# OMODRI_Support.net
KiCad netlist of a schematic drawn in Altium Designer
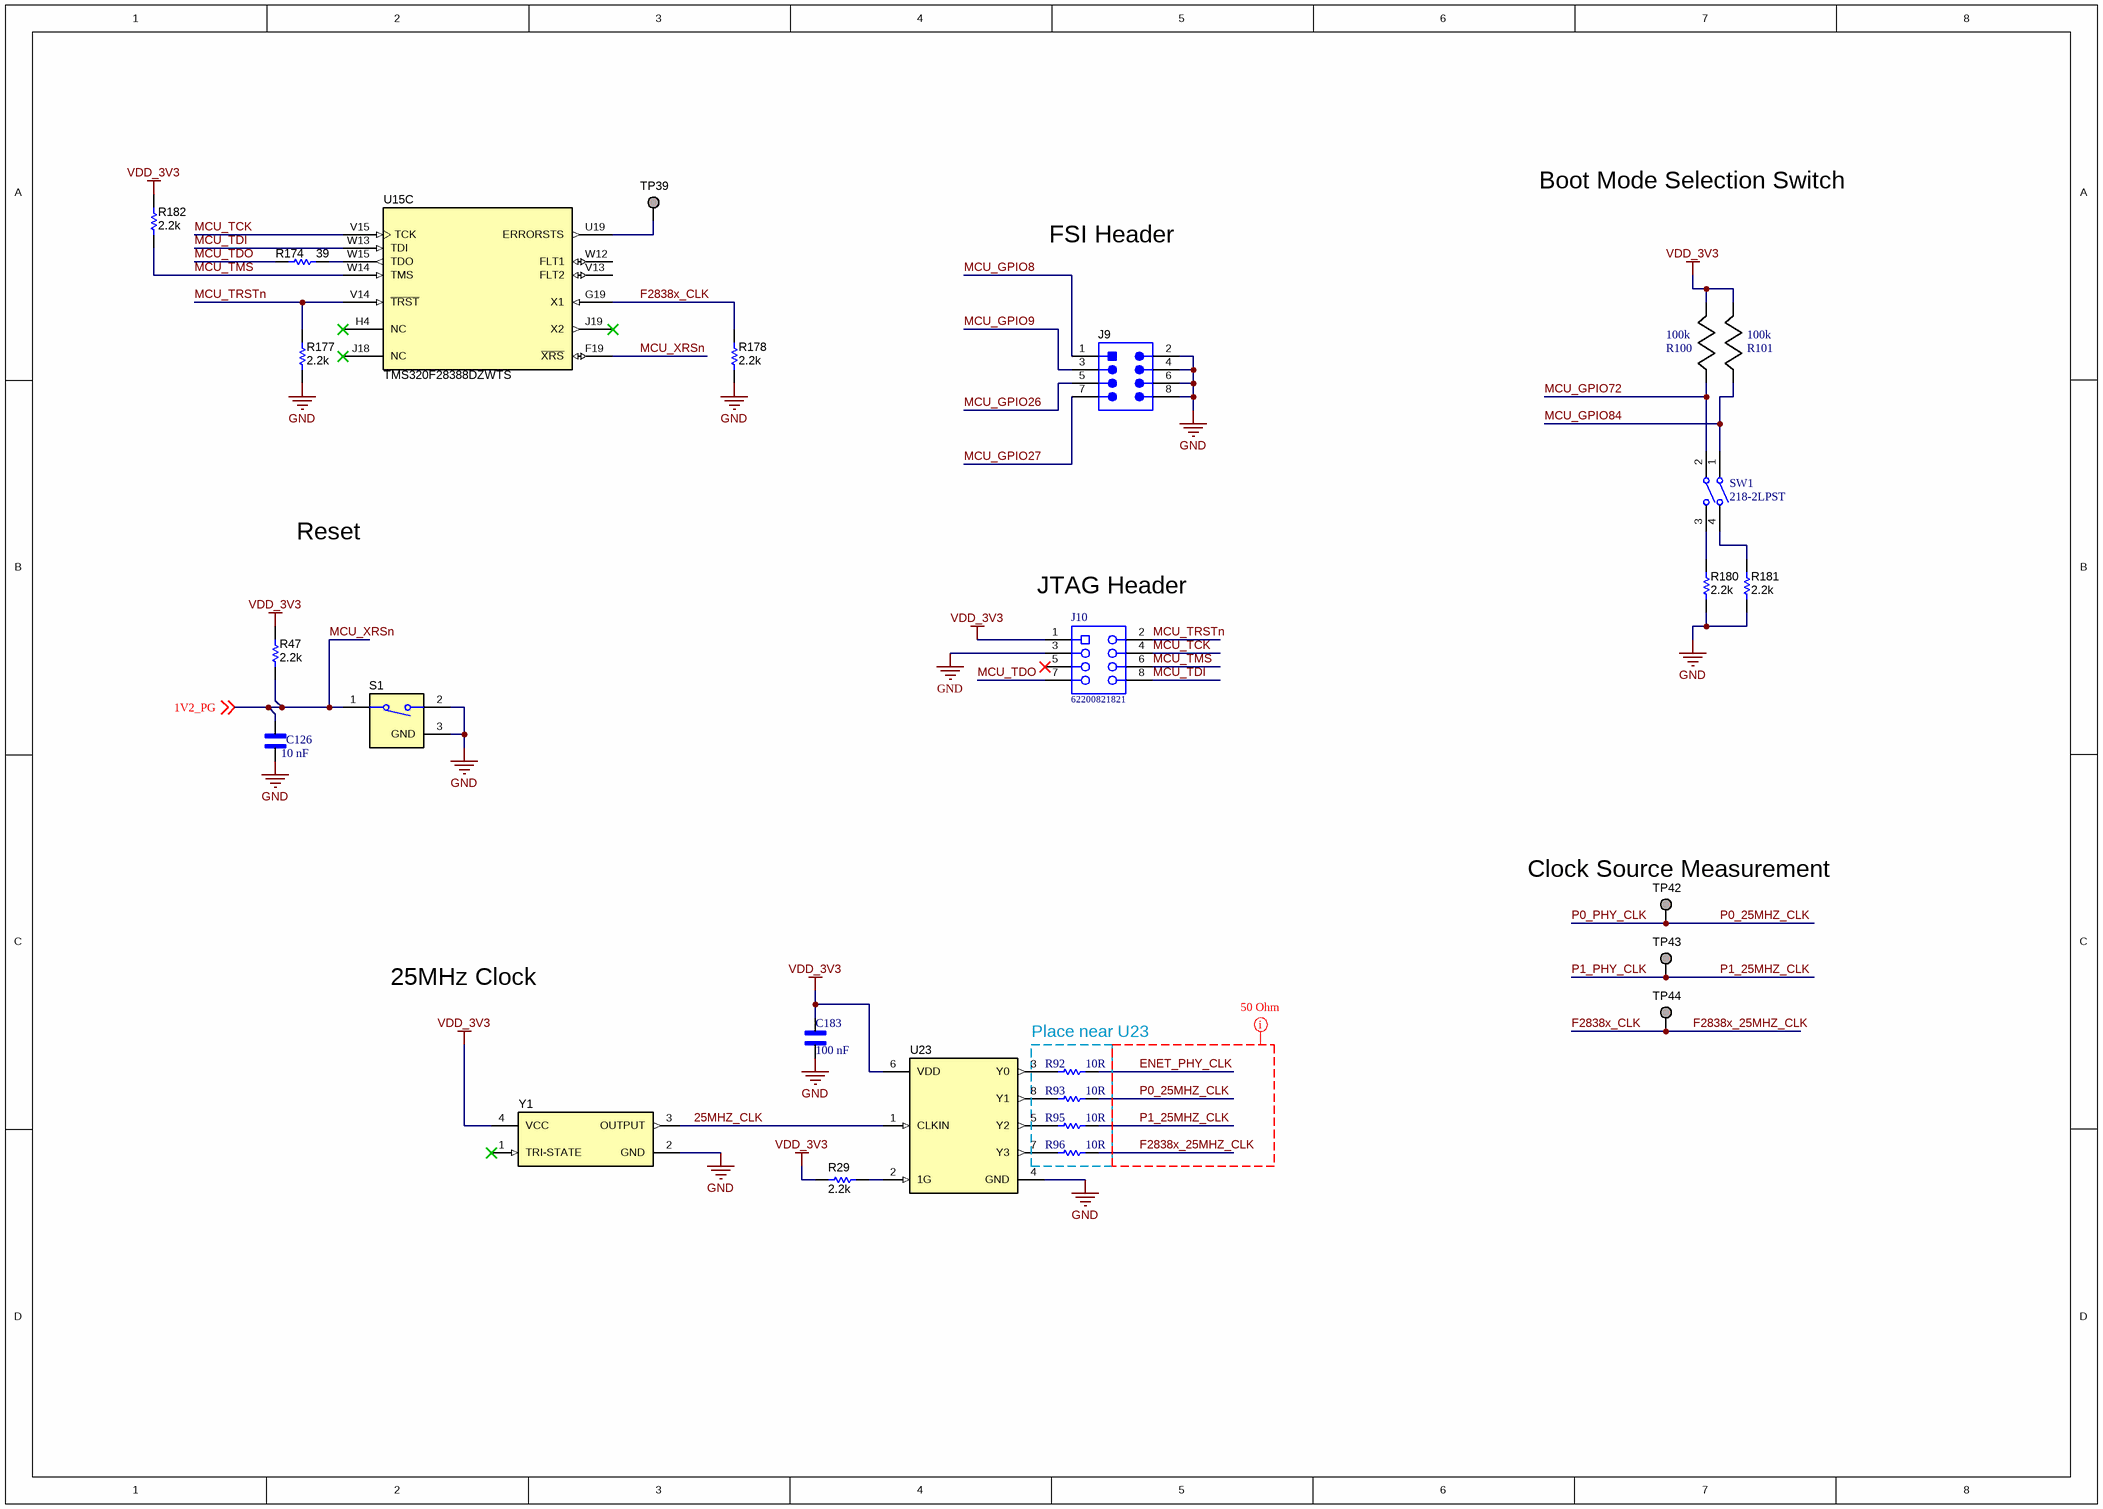
[diagram p0: OMODRI_Support.SchDoc]

(export (version "E")
  (design (tool "Eeschema 10.0.6"))
  (components
    (comp (ref "C126")
      (value "10 nF")
      (footprint "CAPC0603X33N")
      (description "SMD Capacitor X7R_EIA_ with Capacitance: 10000pF Tol. 10%. Rated Voltage: 25Vdc")
      (fields (field (name "MP") "GRM033R71E103KE14D") (field (name "MF") "Murata"))
      (libsource (lib "GRM033R71E103KE14D") (part "GRM033R71E103KE14D"))
    )
    (comp (ref "C183")
      (value "100 nF")
      (footprint "CAPC0603X33N")
      (description "SMD Capacitor X5R_EIA_ with Capacitance: 0.10uF Tol. 10%. Rated Voltage: 25Vdc")
      (fields (field (name "MF") "Murata") (field (name "MP") "GRM033R61E104KE14D"))
      (libsource (lib "GRM033R61E104KE14D") (part "GRM033R61E104KE14D"))
    )
    (comp (ref "J9")
      (value "TMM-104-01-T-D")
      (footprint "Samtec_TMM-104-01-x-D")
      (description "Header, 2mm, 4x2, Tin, TH")
      (fields (field (name "MANUFACTURER") "Samtec"))
      (libsource (lib "Altium Vault - TI") (part "Header_4x2"))
    )
    (comp (ref "J10")
      (value "62200821821")
      (footprint "62200821821")
      (description "THT Vertical Socket Header WR-PHD, Pitch 1.27 mm, Dual Row, 8 pins")
      (fields (field (name "MANUFACTURER") "Wurth Elektronik") (field (name "PUBLISHER") "WurthElektronik"))
      (libsource (lib "Altium Content Vault") (part "WE-CN-2P-F-R8"))
    )
    (comp (ref "R29")
      (value "CRCW04022K20JNED")
      (footprint "0402")
      (description "RES, 2.2 k, 5%, 0.063 W, AEC-Q200 Grade 0, 0402")
      (fields (field (name "MANUFACTURER") "Vishay-Dale") (field (name "VALUEDISPLAYED") "2.2k"))
      (libsource (lib "Altium Vault - TI") (part "Resistor"))
    )
    (comp (ref "R47")
      (value "CRCW04022K20JNED")
      (footprint "0402")
      (description "RES, 2.2 k, 5%, 0.063 W, AEC-Q200 Grade 0, 0402")
      (fields (field (name "MANUFACTURER") "Vishay-Dale") (field (name "VALUEDISPLAYED") "2.2k"))
      (libsource (lib "Altium Vault - TI") (part "Resistor"))
    )
    (comp (ref "R92")
      (value "CRCW040210R0FKEDHP")
      (footprint "RESC1005X40X25ML05T10")
      (description "SMD Chip Resistor, 0402 [1005 Metric], 10 ohm, CRCW-HP e3 Series, 50 V, Thick Film, 200 mW")
      (fields
        (field (name "MANUFACTURER") "Vishay Dale")
        (field (name "TOLERANCE") "1%")
        (field (name "RESISTANCE") "10R")
      )
      (libsource (lib "Vishay-Resistor") (part "CRCW040210R0FKEDHP"))
    )
    (comp (ref "R93")
      (value "CRCW040210R0FKEDHP")
      (footprint "RESC1005X40X25ML05T10")
      (description "SMD Chip Resistor, 0402 [1005 Metric], 10 ohm, CRCW-HP e3 Series, 50 V, Thick Film, 200 mW")
      (fields
        (field (name "MANUFACTURER") "Vishay Dale")
        (field (name "TOLERANCE") "1%")
        (field (name "RESISTANCE") "10R")
      )
      (libsource (lib "Vishay-Resistor") (part "CRCW040210R0FKEDHP"))
    )
    (comp (ref "R95")
      (value "CRCW040210R0FKEDHP")
      (footprint "RESC1005X40X25ML05T10")
      (description "SMD Chip Resistor, 0402 [1005 Metric], 10 ohm, CRCW-HP e3 Series, 50 V, Thick Film, 200 mW")
      (fields
        (field (name "MANUFACTURER") "Vishay Dale")
        (field (name "TOLERANCE") "1%")
        (field (name "RESISTANCE") "10R")
      )
      (libsource (lib "Vishay-Resistor") (part "CRCW040210R0FKEDHP"))
    )
    (comp (ref "R96")
      (value "CRCW040210R0FKEDHP")
      (footprint "RESC1005X40X25ML05T10")
      (description "SMD Chip Resistor, 0402 [1005 Metric], 10 ohm, CRCW-HP e3 Series, 50 V, Thick Film, 200 mW")
      (fields
        (field (name "MANUFACTURER") "Vishay Dale")
        (field (name "TOLERANCE") "1%")
        (field (name "RESISTANCE") "10R")
      )
      (libsource (lib "Vishay-Resistor") (part "CRCW040210R0FKEDHP"))
    )
    (comp (ref "R100")
      (value "CRCW0402100KFKED")
      (footprint "0402")
      (description "Res Thick Film 0402 100K Ohm 1% 1/16W 100ppm/C Molded SMD Paper T/R")
      (fields
        (field (name "MANUFACTURER") "Vishay")
        (field (name "TOLERANCE") "1%")
        (field (name "RESISTANCE") "100k")
      )
      (libsource (lib "TI_TPS_6208833") (part "CRCW0402100KFKED"))
    )
    (comp (ref "R101")
      (value "CRCW0402100KFKED")
      (footprint "0402")
      (description "Res Thick Film 0402 100K Ohm 1% 1/16W 100ppm/C Molded SMD Paper T/R")
      (fields
        (field (name "MANUFACTURER") "Vishay")
        (field (name "TOLERANCE") "1%")
        (field (name "RESISTANCE") "100k")
      )
      (libsource (lib "TI_TPS_6208833") (part "CRCW0402100KFKED"))
    )
    (comp (ref "R174")
      (value "CRCW040239R0JNED")
      (footprint "0402")
      (description "RES, 39, 5%, 0.063 W, AEC-Q200 Grade 0, 0402")
      (fields (field (name "MANUFACTURER") "Vishay-Dale") (field (name "VALUEDISPLAYED") "39"))
      (libsource (lib "Altium Vault - TI") (part "Resistor"))
    )
    (comp (ref "R177")
      (value "CRCW04022K20JNED")
      (footprint "0402")
      (description "RES, 2.2 k, 5%, 0.063 W, AEC-Q200 Grade 0, 0402")
      (fields (field (name "MANUFACTURER") "Vishay-Dale") (field (name "VALUEDISPLAYED") "2.2k"))
      (libsource (lib "Altium Vault - TI") (part "Resistor"))
    )
    (comp (ref "R178")
      (value "CRCW04022K20JNED")
      (footprint "0402")
      (description "RES, 2.2 k, 5%, 0.063 W, AEC-Q200 Grade 0, 0402")
      (fields (field (name "MANUFACTURER") "Vishay-Dale") (field (name "VALUEDISPLAYED") "2.2k"))
      (libsource (lib "Altium Vault - TI") (part "Resistor"))
    )
    (comp (ref "R180")
      (value "CRCW04022K20JNED")
      (footprint "0402")
      (description "RES, 2.2 k, 5%, 0.063 W, AEC-Q200 Grade 0, 0402")
      (fields (field (name "VALUEDISPLAYED") "2.2k") (field (name "MANUFACTURER") "Vishay-Dale"))
      (libsource (lib "Altium Vault - TI") (part "Resistor"))
    )
    (comp (ref "R181")
      (value "CRCW04022K20JNED")
      (footprint "0402")
      (description "RES, 2.2 k, 5%, 0.063 W, AEC-Q200 Grade 0, 0402")
      (fields (field (name "VALUEDISPLAYED") "2.2k") (field (name "MANUFACTURER") "Vishay-Dale"))
      (libsource (lib "Altium Vault - TI") (part "Resistor"))
    )
    (comp (ref "R182")
      (value "CRCW04022K20JNED")
      (footprint "0402")
      (description "RES, 2.2 k, 5%, 0.063 W, AEC-Q200 Grade 0, 0402")
      (fields (field (name "MANUFACTURER") "Vishay-Dale") (field (name "VALUEDISPLAYED") "2.2k"))
      (libsource (lib "Altium Vault - TI") (part "Resistor"))
    )
    (comp (ref "S1")
      (value "B3U-1100P")
      (footprint "SW_B3U-1100P")
      (description "Switch, SPST-NO, Off-Mom, 12 V, SMD")
      (fields
        (field (name "MANUFACTURER") "Omron Electronic Components")
        (field (name "PUBLISHER") "Texas Instruments")
      )
      (libsource (lib "Altium Vault - TI") (part "Switch_PushButton_GND3"))
    )
    (comp (ref "SW1")
      (value "218-2LPST")
      (footprint "CTS-218-2LPST_V")
      (description "Half Pitch DIP Switch Auto Placeable, 25 mA, 24 V, -55 to 85 degC, 4-Pin SMD, RoHS, Tube")
      (fields (field (name "MANUFACTURER") "CTS Corporation"))
      (libsource (lib "Altium Content Vault") (part "SW-SPST-4_C"))
    )
    (comp (ref "TP39")
      (value "TESTPOINT")
      (footprint "TP_50MIL-25MILHOLE")
      (description "TEST POINT.  No entry in BOM.")
      (libsource (lib "Altium Vault - TI") (part "CMP-0078143-2"))
    )
    (comp (ref "TP42")
      (value "TESTPOINT")
      (footprint "TP_50MIL-25MILHOLE")
      (description "TEST POINT.  No entry in BOM.")
      (libsource (lib "Altium Vault - TI") (part "CMP-0078143-2"))
    )
    (comp (ref "TP43")
      (value "TESTPOINT")
      (footprint "TP_50MIL-25MILHOLE")
      (description "TEST POINT.  No entry in BOM.")
      (libsource (lib "Altium Vault - TI") (part "CMP-0078143-2"))
    )
    (comp (ref "TP44")
      (value "TESTPOINT")
      (footprint "TP_50MIL-25MILHOLE")
      (description "TEST POINT.  No entry in BOM.")
      (libsource (lib "Altium Vault - TI") (part "CMP-0078143-2"))
    )
    (comp (ref "U15")
      (value "TMS320F28388DZWTS")
      (footprint "ZWT0337A")
      (description "TMS320F28388DZWTS, ZWT0337A (NFBGA-337)")
      (fields
        (field (name "PARTNUMBER") "TMS320F28388DZWTS")
        (field (name "MANUFACTURER") "Texas Instruments")
      )
      (libsource (lib "Altium Vault - TI") (part "TMS320F28388"))
    )
    (comp (ref "U23")
      (value "CDCLVC1104PW")
      (footprint "PW0008A_N")
      (description "Low Jitter, 1:4 LVCMOS Fan-out Clock Buffer, PW0008A (TSSOP-8)")
      (fields
        (field (name "MANUFACTURER") "Texas Instruments")
        (field (name "PUBLISHER") "Texas Instruments")
      )
      (libsource (lib "Altium Vault - TI") (part "CDCLVC1104"))
    )
    (comp (ref "Y1")
      (value "ECS-2520S33-250-FN-TR")
      (footprint "ECS_ECS-2520S")
      (description "Oscillator, 25 MHz, 15 pF, SMD")
      (fields (field (name "MANUFACTURER") "ECS Inc."))
      (libsource (lib "Altium Vault - TI") (part "OSC_4P_1_TRI-STATE"))
    )
  )
  (nets
    (net (code "1") (name "/25MHZ_CLK") (class "Default")
      (node (ref "U23") (pin "1") (pinfunction "CLKIN_1") (pintype "input"))
      (node (ref "Y1") (pin "3") (pinfunction "OUTPUT_3") (pintype "output"))
    )
    (net (code "2") (name "/ENET_PHY_CLK") (class "Default")
      (node (ref "R92") (pin "2") (pinfunction "2_2") (pintype "passive"))
    )
    (net (code "3") (name "/F2838x_25MHZ_CLK") (class "Default")
      (node (ref "R178") (pin "2") (pinfunction "2_2") (pintype "passive"))
      (node (ref "R96") (pin "2") (pinfunction "2_2") (pintype "passive"))
      (node (ref "TP44") (pin "1") (pintype "passive"))
      (node (ref "U15") (pin "G19") (pinfunction "X1_G19") (pintype "input"))
    )
    (net (code "4") (name "/MCU_GPIO8") (class "Default")
      (node (ref "J9") (pin "1") (pinfunction "1_1") (pintype "passive"))
    )
    (net (code "5") (name "/MCU_GPIO9") (class "Default")
      (node (ref "J9") (pin "3") (pinfunction "3_3") (pintype "passive"))
    )
    (net (code "6") (name "/MCU_GPIO26") (class "Default")
      (node (ref "J9") (pin "5") (pinfunction "5_5") (pintype "passive"))
    )
    (net (code "7") (name "/MCU_GPIO27") (class "Default")
      (node (ref "J9") (pin "7") (pinfunction "7_7") (pintype "passive"))
    )
    (net (code "8") (name "/MCU_GPIO72") (class "Default")
      (node (ref "R100") (pin "2") (pinfunction "2_2") (pintype "passive"))
      (node (ref "SW1") (pin "2") (pinfunction "2_2") (pintype "passive"))
    )
    (net (code "9") (name "/MCU_GPIO84") (class "Default")
      (node (ref "R101") (pin "2") (pinfunction "2_2") (pintype "passive"))
      (node (ref "SW1") (pin "1") (pinfunction "1_1") (pintype "passive"))
    )
    (net (code "10") (name "/MCU_TCK") (class "Default")
      (node (ref "J10") (pin "4") (pinfunction "4_4") (pintype "passive"))
      (node (ref "U15") (pin "V15") (pinfunction "TCK_V15") (pintype "input"))
    )
    (net (code "11") (name "/MCU_TDI") (class "Default")
      (node (ref "J10") (pin "8") (pinfunction "8_8") (pintype "passive"))
      (node (ref "U15") (pin "W13") (pinfunction "TDI_W13") (pintype "input"))
    )
    (net (code "12") (name "/MCU_TDO") (class "Default")
      (node (ref "J10") (pin "7") (pinfunction "7_7") (pintype "passive"))
      (node (ref "R174") (pin "1") (pinfunction "1_1") (pintype "passive"))
    )
    (net (code "13") (name "/MCU_TMS") (class "Default")
      (node (ref "J10") (pin "6") (pinfunction "6_6") (pintype "passive"))
      (node (ref "R182") (pin "1") (pinfunction "1_1") (pintype "passive"))
      (node (ref "U15") (pin "W14") (pinfunction "TMS_W14") (pintype "input"))
    )
    (net (code "14") (name "/MCU_TRSTn") (class "Default")
      (node (ref "J10") (pin "2") (pinfunction "2_2") (pintype "passive"))
      (node (ref "R177") (pin "2") (pinfunction "2_2") (pintype "passive"))
      (node (ref "U15") (pin "V14") (pinfunction "TRST_V14") (pintype "input"))
    )
    (net (code "15") (name "/P0_25MHZ_CLK") (class "Default")
      (node (ref "R93") (pin "2") (pinfunction "2_2") (pintype "passive"))
      (node (ref "TP42") (pin "1") (pintype "passive"))
    )
    (net (code "16") (name "/P1_25MHZ_CLK") (class "Default")
      (node (ref "R95") (pin "2") (pinfunction "2_2") (pintype "passive"))
      (node (ref "TP43") (pin "1") (pintype "passive"))
    )
    (net (code "17") (name "1V2_PG") (class "Default")
      (node (ref "C126") (pin "2") (pinfunction "2_2") (pintype "passive"))
      (node (ref "R47") (pin "1") (pinfunction "1_1") (pintype "passive"))
      (node (ref "S1") (pin "1") (pinfunction "1_1") (pintype "passive"))
      (node (ref "U15") (pin "F19") (pinfunction "XRS_F19") (pintype "bidirectional"))
    )
    (net (code "18") (name "GND") (class "Default")
      (node (ref "C126") (pin "1") (pinfunction "1_1") (pintype "passive"))
      (node (ref "C183") (pin "2") (pinfunction "2_2") (pintype "passive"))
      (node (ref "J10") (pin "3") (pinfunction "3_3") (pintype "passive"))
      (node (ref "J9") (pin "2") (pinfunction "2_2") (pintype "passive"))
      (node (ref "J9") (pin "4") (pinfunction "4_4") (pintype "passive"))
      (node (ref "J9") (pin "6") (pinfunction "6_6") (pintype "passive"))
      (node (ref "J9") (pin "8") (pinfunction "8_8") (pintype "passive"))
      (node (ref "R177") (pin "1") (pinfunction "1_1") (pintype "passive"))
      (node (ref "R178") (pin "1") (pinfunction "1_1") (pintype "passive"))
      (node (ref "R180") (pin "2") (pinfunction "2_2") (pintype "passive"))
      (node (ref "R181") (pin "1") (pinfunction "1_1") (pintype "passive"))
      (node (ref "S1") (pin "2") (pinfunction "2_2") (pintype "passive"))
      (node (ref "S1") (pin "3") (pinfunction "GND_3") (pintype "power_in"))
      (node (ref "U23") (pin "4") (pinfunction "GND_4") (pintype "power_in"))
      (node (ref "Y1") (pin "2") (pinfunction "GND_2") (pintype "power_in"))
    )
    (net (code "19") (name "Net-(R180-Pad1)") (class "Default")
      (node (ref "R180") (pin "1") (pinfunction "1_1") (pintype "passive"))
      (node (ref "SW1") (pin "3") (pinfunction "3_3") (pintype "passive"))
    )
    (net (code "20") (name "Net-(R181-Pad2)") (class "Default")
      (node (ref "R181") (pin "2") (pinfunction "2_2") (pintype "passive"))
      (node (ref "SW1") (pin "4") (pinfunction "4_4") (pintype "passive"))
    )
    (net (code "21") (name "Net-(U15C-ERRORSTS)") (class "Default")
      (node (ref "TP39") (pin "1") (pintype "passive"))
      (node (ref "U15") (pin "U19") (pinfunction "ERRORSTS_U19") (pintype "output"))
    )
    (net (code "22") (name "Net-(U15C-TDO)") (class "Default")
      (node (ref "R174") (pin "2") (pinfunction "2_2") (pintype "passive"))
      (node (ref "U15") (pin "W15") (pinfunction "TDO_W15") (pintype "output"))
    )
    (net (code "23") (name "Net-(U23-1G)") (class "Default")
      (node (ref "R29") (pin "1") (pinfunction "1_1") (pintype "passive"))
      (node (ref "U23") (pin "2") (pinfunction "1G_2") (pintype "input"))
    )
    (net (code "24") (name "Net-(U23-Y0)") (class "Default")
      (node (ref "R92") (pin "1") (pinfunction "1_1") (pintype "passive"))
      (node (ref "U23") (pin "3") (pinfunction "Y0_3") (pintype "output"))
    )
    (net (code "25") (name "Net-(U23-Y1)") (class "Default")
      (node (ref "R93") (pin "1") (pinfunction "1_1") (pintype "passive"))
      (node (ref "U23") (pin "8") (pinfunction "Y1_8") (pintype "output"))
    )
    (net (code "26") (name "Net-(U23-Y2)") (class "Default")
      (node (ref "R95") (pin "1") (pinfunction "1_1") (pintype "passive"))
      (node (ref "U23") (pin "5") (pinfunction "Y2_5") (pintype "output"))
    )
    (net (code "27") (name "Net-(U23-Y3)") (class "Default")
      (node (ref "R96") (pin "1") (pinfunction "1_1") (pintype "passive"))
      (node (ref "U23") (pin "7") (pinfunction "Y3_7") (pintype "output"))
    )
    (net (code "28") (name "VDD_3V3") (class "Default")
      (node (ref "C183") (pin "1") (pinfunction "1_1") (pintype "passive"))
      (node (ref "J10") (pin "1") (pinfunction "1_1") (pintype "passive"))
      (node (ref "R100") (pin "1") (pinfunction "1_1") (pintype "passive"))
      (node (ref "R101") (pin "1") (pinfunction "1_1") (pintype "passive"))
      (node (ref "R182") (pin "2") (pinfunction "2_2") (pintype "passive"))
      (node (ref "R29") (pin "2") (pinfunction "2_2") (pintype "passive"))
      (node (ref "R47") (pin "2") (pinfunction "2_2") (pintype "passive"))
      (node (ref "U23") (pin "6") (pinfunction "VDD_6") (pintype "power_in"))
      (node (ref "Y1") (pin "4") (pinfunction "VCC_4") (pintype "power_in"))
    )
    (net (code "29") (name "unconnected-(J10-Pad5)") (class "Default")
      (node (ref "J10") (pin "5") (pinfunction "5_5") (pintype "passive+no_connect"))
    )
    (net (code "30") (name "unconnected-(U15C-FLT1-PadW12)") (class "Default")
      (node (ref "U15") (pin "W12") (pinfunction "FLT1_W12") (pintype "bidirectional"))
    )
    (net (code "31") (name "unconnected-(U15C-FLT2-PadV13)") (class "Default")
      (node (ref "U15") (pin "V13") (pinfunction "FLT2_V13") (pintype "bidirectional"))
    )
    (net (code "32") (name "unconnected-(U15C-NC-PadH4)") (class "Default")
      (node (ref "U15") (pin "H4") (pinfunction "NC_H4") (pintype "passive+no_connect"))
    )
    (net (code "33") (name "unconnected-(U15C-NC-PadJ18)") (class "Default")
      (node (ref "U15") (pin "J18") (pinfunction "NC_J18") (pintype "passive+no_connect"))
    )
    (net (code "34") (name "unconnected-(U15C-X2-PadJ19)") (class "Default")
      (node (ref "U15") (pin "J19") (pinfunction "X2_J19") (pintype "output+no_connect"))
    )
    (net (code "35") (name "unconnected-(Y1-TRI-STATE-Pad1)") (class "Default")
      (node (ref "Y1") (pin "1") (pinfunction "TRI-STATE_1") (pintype "input+no_connect"))
    )
  )
)
